# light_sensor.net
KiCad netlist of a schematic drawn in Altium Designer
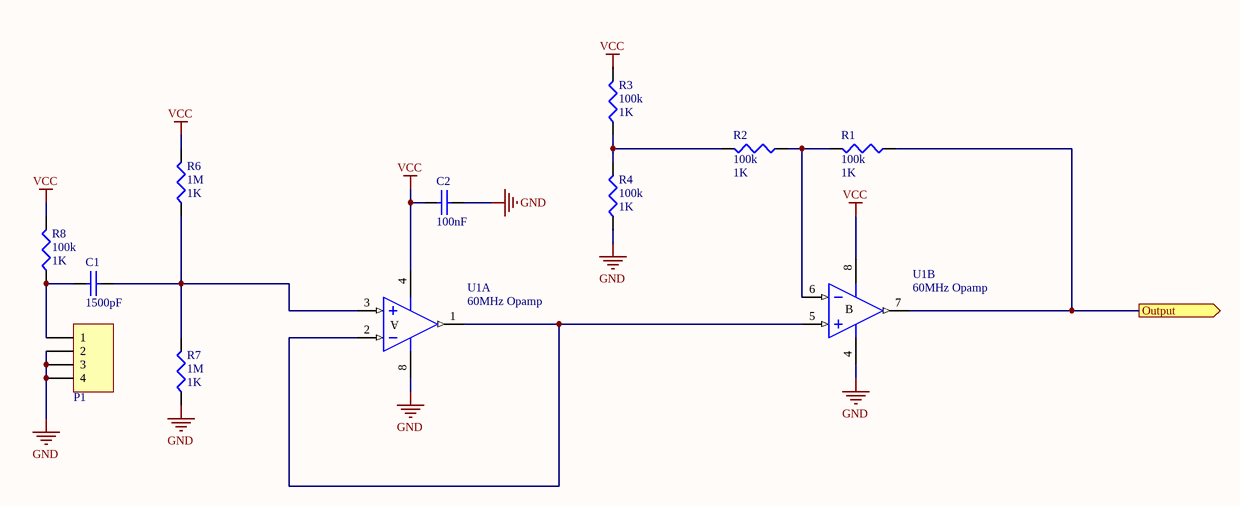
[diagram p0: light_sensor.SchDoc]

(export (version "E")
  (design (tool "Eeschema 10.0.6"))
  (components
    (comp (ref "C1")
      (value "1500pF")
      (footprint "ECE-CAPC1608-0603SM")
      (description "CAP CER 1500pF 50V X7R SM0603")
      (libsource (lib "EceParts") (part "Cap"))
    )
    (comp (ref "C2")
      (value "100nF")
      (footprint "ECE-CAPC1608-0603SM")
      (description "CAP CER 100nF 25V X7R SM0603")
      (libsource (lib "EceParts") (part "Cap"))
    )
    (comp (ref "P1")
      (value "Phototransistor")
      (footprint "ECE-600104STTH")
      (description "HEADER POLARISED 4WAY TH")
      (libsource (lib "EceParts") (part "Header 4"))
    )
    (comp (ref "R1")
      (value "100k")
      (footprint "J1-0603")
      (description "Resistor")
      (fields (field (name "ALTIUM_VALUE") "1K") (field (name "PUBLISHER") "Altium Limited"))
      (libsource (lib "Miscellaneous Devices") (part "Res3"))
    )
    (comp (ref "R2")
      (value "100k")
      (footprint "J1-0603")
      (description "Resistor")
      (fields (field (name "ALTIUM_VALUE") "1K") (field (name "PUBLISHER") "Altium Limited"))
      (libsource (lib "Miscellaneous Devices") (part "Res3"))
    )
    (comp (ref "R3")
      (value "100k")
      (footprint "J1-0603")
      (description "Resistor")
      (fields (field (name "ALTIUM_VALUE") "1K") (field (name "PUBLISHER") "Altium Limited"))
      (libsource (lib "Miscellaneous Devices") (part "Res3"))
    )
    (comp (ref "R4")
      (value "100k")
      (footprint "J1-0603")
      (description "Resistor")
      (fields (field (name "ALTIUM_VALUE") "1K") (field (name "PUBLISHER") "Altium Limited"))
      (libsource (lib "Miscellaneous Devices") (part "Res3"))
    )
    (comp (ref "R6")
      (value "1M")
      (footprint "J1-0603")
      (description "Resistor")
      (fields (field (name "ALTIUM_VALUE") "1K") (field (name "PUBLISHER") "Altium Limited"))
      (libsource (lib "Miscellaneous Devices") (part "Res3"))
    )
    (comp (ref "R7")
      (value "1M")
      (footprint "J1-0603")
      (description "Resistor")
      (fields (field (name "ALTIUM_VALUE") "1K") (field (name "PUBLISHER") "Altium Limited"))
      (libsource (lib "Miscellaneous Devices") (part "Res3"))
    )
    (comp (ref "R8")
      (value "100k")
      (footprint "J1-0603")
      (description "Resistor")
      (fields (field (name "ALTIUM_VALUE") "1K") (field (name "PUBLISHER") "Altium Limited"))
      (libsource (lib "Miscellaneous Devices") (part "Res3"))
    )
    (comp (ref "U1") (value "60MHz Opamp") (footprint "SO-8") (libsource (lib "EE209-SMT") (part "LT6221")))
  )
  (nets
    (net (code "1") (name "/Output") (class "Default")
      (node (ref "R1") (pin "1") (pinfunction "1_1") (pintype "passive"))
      (node (ref "U1") (pin "7") (pinfunction "OUT_7") (pintype "output"))
    )
    (net (code "2") (name "GND") (class "Default")
      (node (ref "C2") (pin "2") (pinfunction "2_2") (pintype "passive"))
      (node (ref "P1") (pin "2") (pinfunction "2_2") (pintype "passive"))
      (node (ref "P1") (pin "3") (pinfunction "3_3") (pintype "passive"))
      (node (ref "P1") (pin "4") (pinfunction "4_4") (pintype "passive"))
      (node (ref "R4") (pin "1") (pinfunction "1_1") (pintype "passive"))
      (node (ref "R7") (pin "1") (pinfunction "1_1") (pintype "passive"))
      (node (ref "U1") (pin "4") (pinfunction "V-_4") (pintype "power_in"))
      (node (ref "U1") (pin "8") (pinfunction "V+_8") (pintype "power_in"))
    )
    (net (code "3") (name "Net-(C1-Pad2)") (class "Default")
      (node (ref "C1") (pin "2") (pinfunction "2_2") (pintype "passive"))
      (node (ref "P1") (pin "1") (pinfunction "1_1") (pintype "passive"))
      (node (ref "R8") (pin "1") (pinfunction "1_1") (pintype "passive"))
    )
    (net (code "4") (name "Net-(R2-Pad2)") (class "Default")
      (node (ref "R2") (pin "2") (pinfunction "2_2") (pintype "passive"))
      (node (ref "R3") (pin "1") (pinfunction "1_1") (pintype "passive"))
      (node (ref "R4") (pin "2") (pinfunction "2_2") (pintype "passive"))
    )
    (net (code "5") (name "Net-(U1A-IN+)") (class "Default")
      (node (ref "C1") (pin "1") (pinfunction "1_1") (pintype "passive"))
      (node (ref "R6") (pin "1") (pinfunction "1_1") (pintype "passive"))
      (node (ref "R7") (pin "2") (pinfunction "2_2") (pintype "passive"))
      (node (ref "U1") (pin "3") (pinfunction "IN+_3") (pintype "input"))
    )
    (net (code "6") (name "Net-(U1A-IN-)") (class "Default")
      (node (ref "U1") (pin "1") (pinfunction "OUT_1") (pintype "output"))
      (node (ref "U1") (pin "2") (pinfunction "IN-_2") (pintype "input"))
      (node (ref "U1") (pin "5") (pinfunction "IN+_5") (pintype "input"))
    )
    (net (code "7") (name "Net-(U1B-IN-)") (class "Default")
      (node (ref "R1") (pin "2") (pinfunction "2_2") (pintype "passive"))
      (node (ref "R2") (pin "1") (pinfunction "1_1") (pintype "passive"))
      (node (ref "U1") (pin "6") (pinfunction "IN-_6") (pintype "input"))
    )
    (net (code "8") (name "VCC") (class "Default")
      (node (ref "C2") (pin "1") (pinfunction "1_1") (pintype "passive"))
      (node (ref "R3") (pin "2") (pinfunction "2_2") (pintype "passive"))
      (node (ref "R6") (pin "2") (pinfunction "2_2") (pintype "passive"))
      (node (ref "R8") (pin "2") (pinfunction "2_2") (pintype "passive"))
      (node (ref "U1") (pin "4") (pinfunction "V-_4") (pintype "power_in"))
      (node (ref "U1") (pin "8") (pinfunction "V+_8") (pintype "power_in"))
    )
  )
)
